# Microcontroller_CC1350.net
KiCad netlist of a schematic drawn in Altium Designer
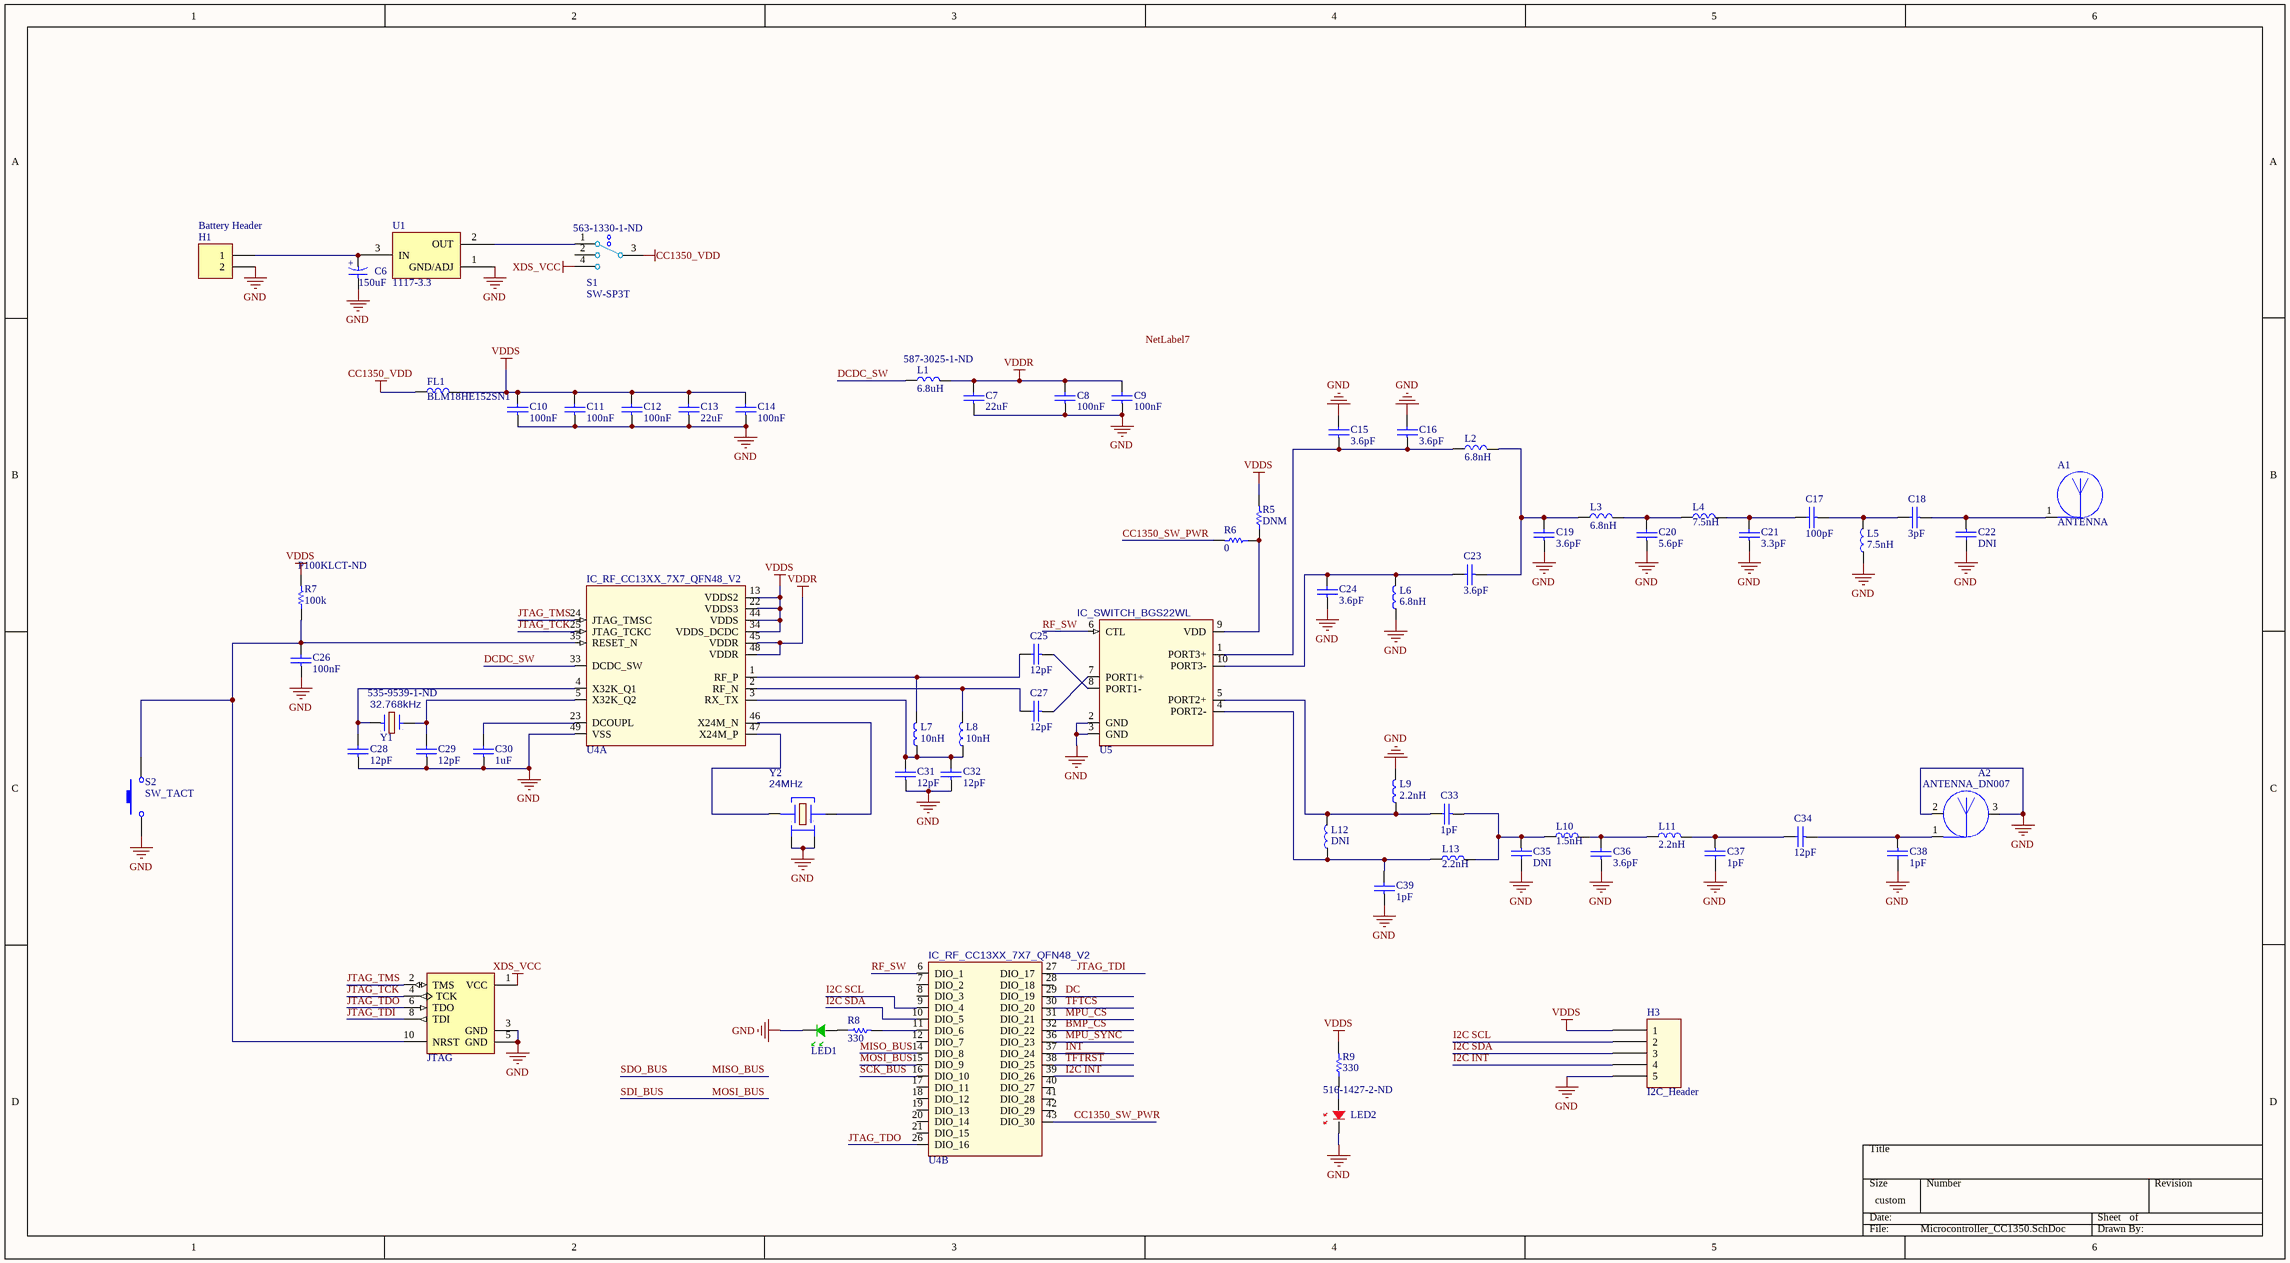
[diagram p0: Microcontroller_CC1350.SchDoc]

(export (version "E")
  (design (tool "Eeschema 10.0.6"))
  (components
    (comp (ref "A1")
      (value "ANTENNA")
      (footprint "Sub-1GHz-Antenna")
      (fields (field (name "DESIGNED BY") "Pawel Kwaskiewicz"))
      (libsource (lib "Biosense_Altium_Library") (part "ANTENNA"))
    )
    (comp (ref "A2")
      (value "ANTENNA_DN007")
      (footprint "Inverted_F_Antenna")
      (fields (field (name "DESIGNED BY") "Artur Bielinski"))
      (libsource (lib "Biosense_Altium_Library") (part "ANTENNA_DN007"))
    )
    (comp (ref "C6")
      (value "150uF")
      (footprint "2312 [IMP] Polar")
      (description "Capacitor")
      (libsource (lib "Biosense_Altium_Library") (part "Cap_E"))
    )
    (comp (ref "C7")
      (value "22uF")
      (footprint "0603[IMP]")
      (fields (field (name "VOLTAGE") "CMAX"))
      (libsource (lib "Biosense_Altium_Library") (part "CAPACITOR"))
    )
    (comp (ref "C8")
      (value "100nF")
      (footprint "0402[IMP]")
      (fields (field (name "VOLTAGE") "CMAX"))
      (libsource (lib "Biosense_Altium_Library") (part "CAPACITOR"))
    )
    (comp (ref "C9")
      (value "100nF")
      (footprint "0402[IMP]")
      (fields (field (name "VOLTAGE") "CMAX"))
      (libsource (lib "Biosense_Altium_Library") (part "CAPACITOR"))
    )
    (comp (ref "C10")
      (value "100nF")
      (footprint "0402[IMP]")
      (fields (field (name "VOLTAGE") "CMAX"))
      (libsource (lib "Biosense_Altium_Library") (part "CAPACITOR"))
    )
    (comp (ref "C11")
      (value "100nF")
      (footprint "0402[IMP]")
      (fields (field (name "VOLTAGE") "CMAX"))
      (libsource (lib "Biosense_Altium_Library") (part "CAPACITOR"))
    )
    (comp (ref "C12")
      (value "100nF")
      (footprint "0402[IMP]")
      (fields (field (name "VOLTAGE") "CMAX"))
      (libsource (lib "Biosense_Altium_Library") (part "CAPACITOR"))
    )
    (comp (ref "C13")
      (value "22uF")
      (footprint "0603[IMP]")
      (fields (field (name "VOLTAGE") "CMAX"))
      (libsource (lib "Biosense_Altium_Library") (part "CAPACITOR"))
    )
    (comp (ref "C14")
      (value "100nF")
      (footprint "0402[IMP]")
      (fields (field (name "VOLTAGE") "CMAX"))
      (libsource (lib "Biosense_Altium_Library") (part "CAPACITOR"))
    )
    (comp (ref "C15")
      (value "3.6pF")
      (footprint "0402[IMP]")
      (fields (field (name "VOLTAGE") "CMAX"))
      (libsource (lib "Biosense_Altium_Library") (part "CAPACITOR"))
    )
    (comp (ref "C16")
      (value "3.6pF")
      (footprint "0402[IMP]")
      (fields (field (name "VOLTAGE") "CMAX"))
      (libsource (lib "Biosense_Altium_Library") (part "CAPACITOR"))
    )
    (comp (ref "C17")
      (value "100pF")
      (footprint "0402[IMP]")
      (fields (field (name "VOLTAGE") "CMAX"))
      (libsource (lib "Biosense_Altium_Library") (part "CAPACITOR"))
    )
    (comp (ref "C18")
      (value "3pF")
      (footprint "0402[IMP]")
      (fields (field (name "VOLTAGE") "CMAX"))
      (libsource (lib "Biosense_Altium_Library") (part "CAPACITOR"))
    )
    (comp (ref "C19")
      (value "3.6pF")
      (footprint "0402[IMP]")
      (fields (field (name "VOLTAGE") "CMAX"))
      (libsource (lib "Biosense_Altium_Library") (part "CAPACITOR"))
    )
    (comp (ref "C20")
      (value "5.6pF")
      (footprint "0402[IMP]")
      (fields (field (name "VOLTAGE") "CMAX"))
      (libsource (lib "Biosense_Altium_Library") (part "CAPACITOR"))
    )
    (comp (ref "C21")
      (value "3.3pF")
      (footprint "0402[IMP]")
      (fields (field (name "VOLTAGE") "CMAX"))
      (libsource (lib "Biosense_Altium_Library") (part "CAPACITOR"))
    )
    (comp (ref "C22")
      (value "DNI")
      (footprint "0402[IMP]")
      (fields (field (name "VOLTAGE") "CMAX"))
      (libsource (lib "Biosense_Altium_Library") (part "CAPACITOR"))
    )
    (comp (ref "C23")
      (value "3.6pF")
      (footprint "0402[IMP]")
      (fields (field (name "VOLTAGE") "CMAX"))
      (libsource (lib "Biosense_Altium_Library") (part "CAPACITOR"))
    )
    (comp (ref "C24")
      (value "3.6pF")
      (footprint "0402[IMP]")
      (fields (field (name "VOLTAGE") "CMAX"))
      (libsource (lib "Biosense_Altium_Library") (part "CAPACITOR"))
    )
    (comp (ref "C25")
      (value "12pF")
      (footprint "0402[IMP]")
      (fields (field (name "VOLTAGE") "CMAX"))
      (libsource (lib "Biosense_Altium_Library") (part "CAPACITOR"))
    )
    (comp (ref "C26")
      (value "100nF")
      (footprint "0402[IMP]")
      (fields (field (name "VOLTAGE") "CMAX"))
      (libsource (lib "Biosense_Altium_Library") (part "CAPACITOR"))
    )
    (comp (ref "C27")
      (value "12pF")
      (footprint "0402[IMP]")
      (fields (field (name "VOLTAGE") "CMAX"))
      (libsource (lib "Biosense_Altium_Library") (part "CAPACITOR"))
    )
    (comp (ref "C28")
      (value "12pF")
      (footprint "0402[IMP]")
      (fields (field (name "VOLTAGE") "CMAX"))
      (libsource (lib "Biosense_Altium_Library") (part "CAPACITOR"))
    )
    (comp (ref "C29")
      (value "12pF")
      (footprint "0402[IMP]")
      (fields (field (name "VOLTAGE") "CMAX"))
      (libsource (lib "Biosense_Altium_Library") (part "CAPACITOR"))
    )
    (comp (ref "C30")
      (value "1uF")
      (footprint "0402[IMP]")
      (fields (field (name "VOLTAGE") "CMAX"))
      (libsource (lib "Biosense_Altium_Library") (part "CAPACITOR"))
    )
    (comp (ref "C31")
      (value "12pF")
      (footprint "0402[IMP]")
      (fields (field (name "VOLTAGE") "CMAX"))
      (libsource (lib "Biosense_Altium_Library") (part "CAPACITOR"))
    )
    (comp (ref "C32")
      (value "12pF")
      (footprint "0402[IMP]")
      (fields (field (name "VOLTAGE") "CMAX"))
      (libsource (lib "Biosense_Altium_Library") (part "CAPACITOR"))
    )
    (comp (ref "C33")
      (value "1pF")
      (footprint "0402[IMP]")
      (fields (field (name "VOLTAGE") "CMAX"))
      (libsource (lib "Biosense_Altium_Library") (part "CAPACITOR"))
    )
    (comp (ref "C34")
      (value "12pF")
      (footprint "0402[IMP]")
      (fields (field (name "VOLTAGE") "CMAX"))
      (libsource (lib "Biosense_Altium_Library") (part "CAPACITOR"))
    )
    (comp (ref "C35")
      (value "DNI")
      (footprint "0402[IMP]")
      (fields (field (name "VOLTAGE") "CMAX"))
      (libsource (lib "Biosense_Altium_Library") (part "CAPACITOR"))
    )
    (comp (ref "C36")
      (value "3.6pF")
      (footprint "0402[IMP]")
      (fields (field (name "VOLTAGE") "CMAX"))
      (libsource (lib "Biosense_Altium_Library") (part "CAPACITOR"))
    )
    (comp (ref "C37")
      (value "1pF")
      (footprint "0402[IMP]")
      (fields (field (name "VOLTAGE") "CMAX"))
      (libsource (lib "Biosense_Altium_Library") (part "CAPACITOR"))
    )
    (comp (ref "C38")
      (value "1pF")
      (footprint "0402[IMP]")
      (fields (field (name "VOLTAGE") "CMAX"))
      (libsource (lib "Biosense_Altium_Library") (part "CAPACITOR"))
    )
    (comp (ref "C39")
      (value "1pF")
      (footprint "0402[IMP]")
      (fields (field (name "VOLTAGE") "CMAX"))
      (libsource (lib "Biosense_Altium_Library") (part "CAPACITOR"))
    )
    (comp (ref "FL1")
      (value "BLM18HE152SN1")
      (footprint "0603[IMP]")
      (libsource (lib "Biosense_Altium_Library") (part "INDUCTOR"))
    )
    (comp (ref "H1")
      (value "Battery Header")
      (footprint "S2B-PH-SM4-TB")
      (libsource (lib "Biosense_Altium_Library") (part "Header 2"))
    )
    (comp (ref "H2")
      (value "JTAG")
      (footprint "HDR-2*5-0.05_Without_Through_Hole")
      (description "USB JTAG Programmer")
      (libsource (lib "Biosense_Altium_Library") (part "JTAG-ARM"))
    )
    (comp (ref "H3")
      (value "I2C_Header")
      (footprint "I2C_Header")
      (libsource (lib "Biosense_Altium_Library") (part "I2C_Header"))
    )
    (comp (ref "L1")
      (value "6.8uH")
      (footprint "0805[IMP]")
      (fields (field (name "SUPPLIER PART NUMBER 1") "587-3025-1-ND"))
      (libsource (lib "Biosense_Altium_Library") (part "INDUCTOR"))
    )
    (comp (ref "L2")
      (value "6.8nH")
      (footprint "0402[IMP]")
      (libsource (lib "Biosense_Altium_Library") (part "INDUCTOR"))
    )
    (comp (ref "L3")
      (value "6.8nH")
      (footprint "0402[IMP]")
      (libsource (lib "Biosense_Altium_Library") (part "INDUCTOR"))
    )
    (comp (ref "L4")
      (value "7.5nH")
      (footprint "0402[IMP]")
      (libsource (lib "Biosense_Altium_Library") (part "INDUCTOR"))
    )
    (comp (ref "L5")
      (value "7.5nH")
      (footprint "0402[IMP]")
      (libsource (lib "Biosense_Altium_Library") (part "INDUCTOR"))
    )
    (comp (ref "L6")
      (value "6.8nH")
      (footprint "0402[IMP]")
      (libsource (lib "Biosense_Altium_Library") (part "INDUCTOR"))
    )
    (comp (ref "L7")
      (value "10nH")
      (footprint "0402[IMP]")
      (libsource (lib "Biosense_Altium_Library") (part "INDUCTOR"))
    )
    (comp (ref "L8")
      (value "10nH")
      (footprint "0402[IMP]")
      (libsource (lib "Biosense_Altium_Library") (part "INDUCTOR"))
    )
    (comp (ref "L9")
      (value "2.2nH")
      (footprint "0402[IMP]")
      (libsource (lib "Biosense_Altium_Library") (part "INDUCTOR"))
    )
    (comp (ref "L10")
      (value "1.5nH")
      (footprint "0402[IMP]")
      (libsource (lib "Biosense_Altium_Library") (part "INDUCTOR"))
    )
    (comp (ref "L11")
      (value "2.2nH")
      (footprint "0402[IMP]")
      (libsource (lib "Biosense_Altium_Library") (part "INDUCTOR"))
    )
    (comp (ref "L12")
      (value "DNI")
      (footprint "0402[IMP]")
      (libsource (lib "Biosense_Altium_Library") (part "INDUCTOR"))
    )
    (comp (ref "L13")
      (value "2.2nH")
      (footprint "0402[IMP]")
      (libsource (lib "Biosense_Altium_Library") (part "INDUCTOR"))
    )
    (comp (ref "LED1")
      (value "LEDG")
      (footprint "0805[IMP] - POLAR")
      (description "LED")
      (libsource (lib "Biosense_Altium_Library") (part "LED_G"))
    )
    (comp (ref "LED2")
      (value "LEDR")
      (footprint "0805[IMP] - POLAR")
      (description "LED")
      (fields (field (name "SUPPLIER PART NUMBER 1") "516-1427-2-ND"))
      (libsource (lib "Biosense_Altium_Library") (part "LED_R"))
    )
    (comp (ref "R5")
      (value "DNM")
      (footprint "0402[IMP]")
      (libsource (lib "Biosense_Altium_Library") (part "RESISTOR"))
    )
    (comp (ref "R6")
      (value "0")
      (footprint "0402[IMP]")
      (libsource (lib "Biosense_Altium_Library") (part "RESISTOR"))
    )
    (comp (ref "R7")
      (value "100k")
      (footprint "0402[IMP]")
      (fields (field (name "SUPPLIER PART NUMBER 1") "P100KLCT-ND"))
      (libsource (lib "Biosense_Altium_Library") (part "RESISTOR"))
    )
    (comp (ref "R8")
      (value "330")
      (footprint "0402[IMP]")
      (libsource (lib "Biosense_Altium_Library") (part "RESISTOR"))
    )
    (comp (ref "R9")
      (value "330")
      (footprint "0402[IMP]")
      (libsource (lib "Biosense_Altium_Library") (part "RESISTOR"))
    )
    (comp (ref "S1")
      (value "SW-SP3T")
      (footprint "CL-SB-13B")
      (fields (field (name "SUPPLIER PART NUMBER 1") "563-1330-1-ND"))
      (libsource (lib "Biosense_Altium_Library") (part "SW-SP3T"))
    )
    (comp (ref "S2")
      (value "SW_TACT")
      (footprint "PTS645SH50SMTR92_LFS")
      (description "Tactile switch")
      (libsource (lib "Biosense_Altium_Library") (part "SW_TACT"))
    )
    (comp (ref "U1")
      (value "1117-3.3")
      (footprint "SOT-223")
      (description "3.3V Voltage Regulator")
      (libsource (lib "Biosense_Altium_Library") (part "1117-3.3V"))
    )
    (comp (ref "U4")
      (value "IC_RF_CC13XX_7X7_QFN48_V2")
      (footprint "RGZ(S-PVQFN-N48) - duplicate")
      (fields (field (name "DESIGNED_BY") "Artur Bielinski"))
      (libsource (lib "Biosense_Altium_Library") (part "IC_RF_CC13XX_7X7_QFN48_V2"))
    )
    (comp (ref "U5")
      (value "IC_SWITCH_BGS22WL")
      (footprint "TSLP-10-1")
      (fields (field (name "DESIGNED_BY") "Artur Bielinski"))
      (libsource (lib "Biosense_Altium_Library") (part "IC_SWITCH_XMSSJE3G0PA-00"))
    )
    (comp (ref "Y1")
      (value "32.768kHz")
      (footprint "FC-135")
      (fields (field (name "SUPPLIER PART NUMBER 1") "535-9539-1-ND"))
      (libsource (lib "Biosense_Altium_Library") (part "CRYSTAL"))
    )
    (comp (ref "Y2")
      (value "24MHz")
      (footprint "TSX-3225")
      (libsource (lib "Biosense_Altium_Library") (part "XTAL_4PIN_S"))
    )
  )
  (nets
    (net (code "1") (name "/BMP_CS") (class "Default")
      (node (ref "U4") (pin "32") (pinfunction "DIO_22_32") (pintype "bidirectional"))
    )
    (net (code "2") (name "/CC1350_SW_PWR") (class "Default")
      (node (ref "R6") (pin "2") (pinfunction "2_2") (pintype "passive"))
      (node (ref "U4") (pin "43") (pinfunction "DIO_30_43") (pintype "bidirectional"))
    )
    (net (code "3") (name "/DC") (class "Default")
      (node (ref "U4") (pin "29") (pinfunction "DIO_19_29") (pintype "bidirectional"))
    )
    (net (code "4") (name "/DCDC_SW") (class "Default")
      (node (ref "L1") (pin "1") (pinfunction "1_1") (pintype "passive"))
      (node (ref "U4") (pin "33") (pinfunction "DCDC_SW_33") (pintype "power_in"))
    )
    (net (code "5") (name "/I2C INT") (class "Default")
      (node (ref "H3") (pin "4") (pinfunction "4_4") (pintype "passive"))
      (node (ref "U4") (pin "39") (pinfunction "DIO_26_39") (pintype "bidirectional"))
    )
    (net (code "6") (name "/I2C SCL") (class "Default")
      (node (ref "H3") (pin "2") (pinfunction "2_2") (pintype "passive"))
      (node (ref "U4") (pin "9") (pinfunction "DIO_4_9") (pintype "bidirectional"))
    )
    (net (code "7") (name "/I2C SDA") (class "Default")
      (node (ref "H3") (pin "3") (pinfunction "3_3") (pintype "passive"))
      (node (ref "U4") (pin "10") (pinfunction "DIO_5_10") (pintype "bidirectional"))
    )
    (net (code "8") (name "/INT") (class "Default")
      (node (ref "U4") (pin "37") (pinfunction "DIO_24_37") (pintype "bidirectional"))
    )
    (net (code "9") (name "/JTAG_TCK") (class "Default")
      (node (ref "H2") (pin "4") (pinfunction "TCK_4") (pintype "output"))
      (node (ref "U4") (pin "25") (pinfunction "JTAG_TCKC_25") (pintype "input"))
    )
    (net (code "10") (name "/JTAG_TDI") (class "Default")
      (node (ref "H2") (pin "8") (pinfunction "TDI_8") (pintype "output"))
      (node (ref "U4") (pin "27") (pinfunction "DIO_17_27") (pintype "bidirectional"))
    )
    (net (code "11") (name "/JTAG_TDO") (class "Default")
      (node (ref "H2") (pin "6") (pinfunction "TDO_6") (pintype "input"))
      (node (ref "U4") (pin "26") (pinfunction "DIO_16_26") (pintype "bidirectional"))
    )
    (net (code "12") (name "/JTAG_TMS") (class "Default")
      (node (ref "H2") (pin "2") (pinfunction "TMS_2") (pintype "bidirectional"))
      (node (ref "U4") (pin "24") (pinfunction "JTAG_TMSC_24") (pintype "input"))
    )
    (net (code "13") (name "/MISO_BUS") (class "Default")
      (node (ref "U4") (pin "14") (pinfunction "DIO_8_14") (pintype "bidirectional"))
    )
    (net (code "14") (name "/MOSI_BUS") (class "Default")
      (node (ref "U4") (pin "15") (pinfunction "DIO_9_15") (pintype "bidirectional"))
    )
    (net (code "15") (name "/MPU_CS") (class "Default")
      (node (ref "U4") (pin "31") (pinfunction "DIO_21_31") (pintype "bidirectional"))
    )
    (net (code "16") (name "/MPU_SYNC") (class "Default")
      (node (ref "U4") (pin "36") (pinfunction "DIO_23_36") (pintype "bidirectional"))
    )
    (net (code "18") (name "/RF_SW") (class "Default")
      (node (ref "U4") (pin "6") (pinfunction "DIO_1_6") (pintype "bidirectional"))
      (node (ref "U5") (pin "6") (pinfunction "CTL_6") (pintype "input"))
    )
    (net (code "19") (name "/SCK_BUS") (class "Default")
      (node (ref "U4") (pin "16") (pinfunction "DIO_10_16") (pintype "bidirectional"))
    )
    (net (code "20") (name "/TFTCS") (class "Default")
      (node (ref "U4") (pin "30") (pinfunction "DIO_20_30") (pintype "bidirectional"))
    )
    (net (code "21") (name "/~{TFTRST}") (class "Default")
      (node (ref "U4") (pin "38") (pinfunction "DIO_25_38") (pintype "bidirectional"))
    )
    (net (code "22") (name "CC1350_VDD") (class "Default")
      (node (ref "FL1") (pin "1") (pinfunction "1_1") (pintype "passive"))
      (node (ref "S1") (pin "3") (pinfunction "3_3") (pintype "passive"))
    )
    (net (code "23") (name "GND") (class "Default")
      (node (ref "A2") (pin "2") (pinfunction "GND_2_2") (pintype "passive"))
      (node (ref "A2") (pin "3") (pinfunction "GND_3_3") (pintype "passive"))
      (node (ref "C10") (pin "2") (pinfunction "2_2") (pintype "passive"))
      (node (ref "C11") (pin "2") (pinfunction "2_2") (pintype "passive"))
      (node (ref "C12") (pin "2") (pinfunction "2_2") (pintype "passive"))
      (node (ref "C13") (pin "2") (pinfunction "2_2") (pintype "passive"))
      (node (ref "C14") (pin "2") (pinfunction "2_2") (pintype "passive"))
      (node (ref "C15") (pin "1") (pinfunction "1_1") (pintype "passive"))
      (node (ref "C16") (pin "1") (pinfunction "1_1") (pintype "passive"))
      (node (ref "C19") (pin "2") (pinfunction "2_2") (pintype "passive"))
      (node (ref "C20") (pin "2") (pinfunction "2_2") (pintype "passive"))
      (node (ref "C21") (pin "2") (pinfunction "2_2") (pintype "passive"))
      (node (ref "C22") (pin "1") (pinfunction "1_1") (pintype "passive"))
      (node (ref "C24") (pin "2") (pinfunction "2_2") (pintype "passive"))
      (node (ref "C26") (pin "2") (pinfunction "2_2") (pintype "passive"))
      (node (ref "C28") (pin "2") (pinfunction "2_2") (pintype "passive"))
      (node (ref "C29") (pin "2") (pinfunction "2_2") (pintype "passive"))
      (node (ref "C30") (pin "2") (pinfunction "2_2") (pintype "passive"))
      (node (ref "C31") (pin "2") (pinfunction "2_2") (pintype "passive"))
      (node (ref "C32") (pin "2") (pinfunction "2_2") (pintype "passive"))
      (node (ref "C35") (pin "1") (pinfunction "1_1") (pintype "passive"))
      (node (ref "C36") (pin "2") (pinfunction "2_2") (pintype "passive"))
      (node (ref "C37") (pin "1") (pinfunction "1_1") (pintype "passive"))
      (node (ref "C38") (pin "1") (pinfunction "1_1") (pintype "passive"))
      (node (ref "C39") (pin "2") (pinfunction "2_2") (pintype "passive"))
      (node (ref "C6") (pin "1") (pinfunction "1_1") (pintype "passive"))
      (node (ref "C7") (pin "2") (pinfunction "2_2") (pintype "passive"))
      (node (ref "C8") (pin "2") (pinfunction "2_2") (pintype "passive"))
      (node (ref "C9") (pin "2") (pinfunction "2_2") (pintype "passive"))
      (node (ref "H1") (pin "2") (pinfunction "2_2") (pintype "passive"))
      (node (ref "H2") (pin "3") (pinfunction "GND_3") (pintype "power_in"))
      (node (ref "H2") (pin "5") (pinfunction "GND_5") (pintype "power_in"))
      (node (ref "H3") (pin "5") (pinfunction "5_5") (pintype "passive"))
      (node (ref "L5") (pin "1") (pinfunction "1_1") (pintype "passive"))
      (node (ref "L6") (pin "1") (pinfunction "1_1") (pintype "passive"))
      (node (ref "L9") (pin "2") (pinfunction "2_2") (pintype "passive"))
      (node (ref "LED1") (pin "2") (pinfunction "K_2") (pintype "passive"))
      (node (ref "LED2") (pin "2") (pinfunction "K_2") (pintype "passive"))
      (node (ref "S2") (pin "1") (pinfunction "1_1") (pintype "passive"))
      (node (ref "U1") (pin "1") (pinfunction "GND/ADJ_1") (pintype "passive"))
      (node (ref "U4") (pin "49") (pinfunction "VSS_49") (pintype "power_in"))
      (node (ref "U5") (pin "2") (pinfunction "GND_2") (pintype "power_in"))
      (node (ref "U5") (pin "3") (pinfunction "GND_3") (pintype "power_in"))
      (node (ref "Y2") (pin "2") (pinfunction "2_2") (pintype "power_in"))
      (node (ref "Y2") (pin "4") (pinfunction "4_4") (pintype "power_in"))
    )
    (net (code "24") (name "Net-(A1-FEED{slash}GND_1)") (class "Default")
      (node (ref "A1") (pin "1") (pinfunction "FEED/GND_1_1") (pintype "passive"))
      (node (ref "C18") (pin "2") (pinfunction "2_2") (pintype "passive"))
      (node (ref "C22") (pin "2") (pinfunction "2_2") (pintype "passive"))
    )
    (net (code "25") (name "Net-(A2-FEED_1)") (class "Default")
      (node (ref "A2") (pin "1") (pinfunction "FEED_1_1") (pintype "passive"))
      (node (ref "C34") (pin "2") (pinfunction "2_2") (pintype "passive"))
      (node (ref "C38") (pin "2") (pinfunction "2_2") (pintype "passive"))
    )
    (net (code "26") (name "Net-(C17-Pad1)") (class "Default")
      (node (ref "C17") (pin "1") (pinfunction "1_1") (pintype "passive"))
      (node (ref "C21") (pin "1") (pinfunction "1_1") (pintype "passive"))
      (node (ref "L4") (pin "2") (pinfunction "2_2") (pintype "passive"))
    )
    (net (code "27") (name "Net-(C17-Pad2)") (class "Default")
      (node (ref "C17") (pin "2") (pinfunction "2_2") (pintype "passive"))
      (node (ref "C18") (pin "1") (pinfunction "1_1") (pintype "passive"))
      (node (ref "L5") (pin "2") (pinfunction "2_2") (pintype "passive"))
    )
    (net (code "28") (name "Net-(C19-Pad1)") (class "Default")
      (node (ref "C19") (pin "1") (pinfunction "1_1") (pintype "passive"))
      (node (ref "C23") (pin "2") (pinfunction "2_2") (pintype "passive"))
      (node (ref "L2") (pin "2") (pinfunction "2_2") (pintype "passive"))
      (node (ref "L3") (pin "1") (pinfunction "1_1") (pintype "passive"))
    )
    (net (code "29") (name "Net-(C20-Pad1)") (class "Default")
      (node (ref "C20") (pin "1") (pinfunction "1_1") (pintype "passive"))
      (node (ref "L3") (pin "2") (pinfunction "2_2") (pintype "passive"))
      (node (ref "L4") (pin "1") (pinfunction "1_1") (pintype "passive"))
    )
    (net (code "30") (name "Net-(C33-Pad2)") (class "Default")
      (node (ref "C33") (pin "2") (pinfunction "2_2") (pintype "passive"))
      (node (ref "C35") (pin "2") (pinfunction "2_2") (pintype "passive"))
      (node (ref "L10") (pin "1") (pinfunction "1_1") (pintype "passive"))
      (node (ref "L13") (pin "2") (pinfunction "2_2") (pintype "passive"))
    )
    (net (code "31") (name "Net-(C34-Pad1)") (class "Default")
      (node (ref "C34") (pin "1") (pinfunction "1_1") (pintype "passive"))
      (node (ref "C37") (pin "2") (pinfunction "2_2") (pintype "passive"))
      (node (ref "L11") (pin "2") (pinfunction "2_2") (pintype "passive"))
    )
    (net (code "32") (name "Net-(C36-Pad1)") (class "Default")
      (node (ref "C36") (pin "1") (pinfunction "1_1") (pintype "passive"))
      (node (ref "L10") (pin "2") (pinfunction "2_2") (pintype "passive"))
      (node (ref "L11") (pin "1") (pinfunction "1_1") (pintype "passive"))
    )
    (net (code "33") (name "Net-(H2-NRST)") (class "Default")
      (node (ref "C26") (pin "1") (pinfunction "1_1") (pintype "passive"))
      (node (ref "H2") (pin "10") (pinfunction "NRST_10") (pintype "passive"))
      (node (ref "R7") (pin "1") (pinfunction "1_1") (pintype "passive"))
      (node (ref "S2") (pin "2") (pinfunction "2_2") (pintype "passive"))
      (node (ref "U4") (pin "35") (pinfunction "RESET_N_35") (pintype "input"))
    )
    (net (code "34") (name "Net-(LED1-A)") (class "Default")
      (node (ref "LED1") (pin "1") (pinfunction "A_1") (pintype "passive"))
      (node (ref "R8") (pin "1") (pinfunction "1_1") (pintype "passive"))
    )
    (net (code "35") (name "Net-(LED2-A)") (class "Default")
      (node (ref "LED2") (pin "1") (pinfunction "A_1") (pintype "passive"))
      (node (ref "R9") (pin "1") (pinfunction "1_1") (pintype "passive"))
    )
    (net (code "36") (name "Net-(U1-IN)") (class "Default")
      (node (ref "C6") (pin "2") (pinfunction "2_2") (pintype "passive"))
      (node (ref "H1") (pin "1") (pinfunction "1_1") (pintype "passive"))
      (node (ref "U1") (pin "3") (pinfunction "IN_3") (pintype "passive"))
    )
    (net (code "37") (name "Net-(U1-OUT)") (class "Default")
      (node (ref "S1") (pin "1") (pinfunction "1_1") (pintype "passive"))
      (node (ref "U1") (pin "2") (pinfunction "OUT_2") (pintype "passive"))
    )
    (net (code "38") (name "Net-(U4A-DCOUPL)") (class "Default")
      (node (ref "C30") (pin "1") (pinfunction "1_1") (pintype "passive"))
      (node (ref "U4") (pin "23") (pinfunction "DCOUPL_23") (pintype "passive"))
    )
    (net (code "39") (name "Net-(U4A-RF_N)") (class "Default")
      (node (ref "C27") (pin "1") (pinfunction "1_1") (pintype "passive"))
      (node (ref "L8") (pin "2") (pinfunction "2_2") (pintype "passive"))
      (node (ref "U4") (pin "2") (pinfunction "RF_N_2") (pintype "passive"))
    )
    (net (code "40") (name "Net-(U4A-RF_P)") (class "Default")
      (node (ref "C25") (pin "1") (pinfunction "1_1") (pintype "passive"))
      (node (ref "L7") (pin "2") (pinfunction "2_2") (pintype "passive"))
      (node (ref "U4") (pin "1") (pinfunction "RF_P_1") (pintype "passive"))
    )
    (net (code "41") (name "Net-(U4A-RX_TX)") (class "Default")
      (node (ref "C31") (pin "1") (pinfunction "1_1") (pintype "passive"))
      (node (ref "C32") (pin "1") (pinfunction "1_1") (pintype "passive"))
      (node (ref "L7") (pin "1") (pinfunction "1_1") (pintype "passive"))
      (node (ref "L8") (pin "1") (pinfunction "1_1") (pintype "passive"))
      (node (ref "U4") (pin "3") (pinfunction "RX_TX_3") (pintype "bidirectional"))
    )
    (net (code "42") (name "Net-(U4A-X24M_N)") (class "Default")
      (node (ref "U4") (pin "46") (pinfunction "X24M_N_46") (pintype "passive"))
      (node (ref "Y2") (pin "3") (pinfunction "3_3") (pintype "passive"))
    )
    (net (code "43") (name "Net-(U4A-X24M_P)") (class "Default")
      (node (ref "U4") (pin "47") (pinfunction "X24M_P_47") (pintype "passive"))
      (node (ref "Y2") (pin "1") (pinfunction "1_1") (pintype "passive"))
    )
    (net (code "44") (name "Net-(U4A-X32K_Q1)") (class "Default")
      (node (ref "C28") (pin "1") (pinfunction "1_1") (pintype "passive"))
      (node (ref "U4") (pin "4") (pinfunction "X32K_Q1_4") (pintype "passive"))
      (node (ref "Y1") (pin "1") (pinfunction "1_1") (pintype "passive"))
    )
    (net (code "45") (name "Net-(U4A-X32K_Q2)") (class "Default")
      (node (ref "C29") (pin "1") (pinfunction "1_1") (pintype "passive"))
      (node (ref "U4") (pin "5") (pinfunction "X32K_Q2_5") (pintype "passive"))
      (node (ref "Y1") (pin "2") (pinfunction "2_2") (pintype "passive"))
    )
    (net (code "46") (name "Net-(U4B-DIO_6)") (class "Default")
      (node (ref "R8") (pin "2") (pinfunction "2_2") (pintype "passive"))
      (node (ref "U4") (pin "11") (pinfunction "DIO_6_11") (pintype "bidirectional"))
    )
    (net (code "47") (name "Net-(U5-PORT1+)") (class "Default")
      (node (ref "C27") (pin "2") (pinfunction "2_2") (pintype "passive"))
      (node (ref "U5") (pin "7") (pinfunction "PORT1+_7") (pintype "passive"))
    )
    (net (code "48") (name "Net-(U5-PORT1-)") (class "Default")
      (node (ref "C25") (pin "2") (pinfunction "2_2") (pintype "passive"))
      (node (ref "U5") (pin "8") (pinfunction "PORT1-_8") (pintype "passive"))
    )
    (net (code "49") (name "Net-(U5-PORT2+)") (class "Default")
      (node (ref "C33") (pin "1") (pinfunction "1_1") (pintype "passive"))
      (node (ref "L12") (pin "2") (pinfunction "2_2") (pintype "passive"))
      (node (ref "L9") (pin "1") (pinfunction "1_1") (pintype "passive"))
      (node (ref "U5") (pin "5") (pinfunction "PORT2+_5") (pintype "passive"))
    )
    (net (code "50") (name "Net-(U5-PORT2-)") (class "Default")
      (node (ref "C39") (pin "1") (pinfunction "1_1") (pintype "passive"))
      (node (ref "L12") (pin "1") (pinfunction "1_1") (pintype "passive"))
      (node (ref "L13") (pin "1") (pinfunction "1_1") (pintype "passive"))
      (node (ref "U5") (pin "4") (pinfunction "PORT2-_4") (pintype "passive"))
    )
    (net (code "51") (name "Net-(U5-PORT3+)") (class "Default")
      (node (ref "C15") (pin "2") (pinfunction "2_2") (pintype "passive"))
      (node (ref "C16") (pin "2") (pinfunction "2_2") (pintype "passive"))
      (node (ref "L2") (pin "1") (pinfunction "1_1") (pintype "passive"))
      (node (ref "U5") (pin "1") (pinfunction "PORT3+_1") (pintype "passive"))
    )
    (net (code "52") (name "Net-(U5-PORT3-)") (class "Default")
      (node (ref "C23") (pin "1") (pinfunction "1_1") (pintype "passive"))
      (node (ref "C24") (pin "1") (pinfunction "1_1") (pintype "passive"))
      (node (ref "L6") (pin "2") (pinfunction "2_2") (pintype "passive"))
      (node (ref "U5") (pin "10") (pinfunction "PORT3-_10") (pintype "passive"))
    )
    (net (code "53") (name "Net-(U5-VDD)") (class "Default")
      (node (ref "R5") (pin "1") (pinfunction "1_1") (pintype "passive"))
      (node (ref "R6") (pin "1") (pinfunction "1_1") (pintype "passive"))
      (node (ref "U5") (pin "9") (pinfunction "VDD_9") (pintype "power_in"))
    )
    (net (code "54") (name "VDDR") (class "Default")
      (node (ref "C7") (pin "1") (pinfunction "1_1") (pintype "passive"))
      (node (ref "C8") (pin "1") (pinfunction "1_1") (pintype "passive"))
      (node (ref "C9") (pin "1") (pinfunction "1_1") (pintype "passive"))
      (node (ref "L1") (pin "2") (pinfunction "2_2") (pintype "passive"))
      (node (ref "U4") (pin "45") (pinfunction "VDDR_45") (pintype "power_in"))
      (node (ref "U4") (pin "48") (pinfunction "VDDR_48") (pintype "power_in"))
    )
    (net (code "55") (name "VDDS") (class "Default")
      (node (ref "C10") (pin "1") (pinfunction "1_1") (pintype "passive"))
      (node (ref "C11") (pin "1") (pinfunction "1_1") (pintype "passive"))
      (node (ref "C12") (pin "1") (pinfunction "1_1") (pintype "passive"))
      (node (ref "C13") (pin "1") (pinfunction "1_1") (pintype "passive"))
      (node (ref "C14") (pin "1") (pinfunction "1_1") (pintype "passive"))
      (node (ref "FL1") (pin "2") (pinfunction "2_2") (pintype "passive"))
      (node (ref "H3") (pin "1") (pinfunction "1_1") (pintype "passive"))
      (node (ref "R5") (pin "2") (pinfunction "2_2") (pintype "passive"))
      (node (ref "R7") (pin "2") (pinfunction "2_2") (pintype "passive"))
      (node (ref "R9") (pin "2") (pinfunction "2_2") (pintype "passive"))
      (node (ref "U4") (pin "13") (pinfunction "VDDS2_13") (pintype "power_in"))
      (node (ref "U4") (pin "22") (pinfunction "VDDS3_22") (pintype "power_in"))
      (node (ref "U4") (pin "34") (pinfunction "VDDS_DCDC_34") (pintype "power_in"))
      (node (ref "U4") (pin "44") (pinfunction "VDDS_44") (pintype "power_in"))
    )
    (net (code "56") (name "XDS_VCC") (class "Default")
      (node (ref "H2") (pin "1") (pinfunction "VCC_1") (pintype "power_in"))
      (node (ref "S1") (pin "4") (pinfunction "4_4") (pintype "passive"))
    )
    (net (code "57") (name "unconnected-(S1-Pad2)") (class "Default")
      (node (ref "S1") (pin "2") (pinfunction "2_2") (pintype "passive"))
    )
    (net (code "58") (name "unconnected-(U4B-DIO_2-Pad7)") (class "Default")
      (node (ref "U4") (pin "7") (pinfunction "DIO_2_7") (pintype "bidirectional"))
    )
    (net (code "59") (name "unconnected-(U4B-DIO_3-Pad8)") (class "Default")
      (node (ref "U4") (pin "8") (pinfunction "DIO_3_8") (pintype "bidirectional"))
    )
    (net (code "60") (name "unconnected-(U4B-DIO_7-Pad12)") (class "Default")
      (node (ref "U4") (pin "12") (pinfunction "DIO_7_12") (pintype "bidirectional"))
    )
    (net (code "61") (name "unconnected-(U4B-DIO_11-Pad17)") (class "Default")
      (node (ref "U4") (pin "17") (pinfunction "DIO_11_17") (pintype "bidirectional"))
    )
    (net (code "62") (name "unconnected-(U4B-DIO_12-Pad18)") (class "Default")
      (node (ref "U4") (pin "18") (pinfunction "DIO_12_18") (pintype "bidirectional"))
    )
    (net (code "63") (name "unconnected-(U4B-DIO_13-Pad19)") (class "Default")
      (node (ref "U4") (pin "19") (pinfunction "DIO_13_19") (pintype "bidirectional"))
    )
    (net (code "64") (name "unconnected-(U4B-DIO_14-Pad20)") (class "Default")
      (node (ref "U4") (pin "20") (pinfunction "DIO_14_20") (pintype "bidirectional"))
    )
    (net (code "65") (name "unconnected-(U4B-DIO_15-Pad21)") (class "Default")
      (node (ref "U4") (pin "21") (pinfunction "DIO_15_21") (pintype "bidirectional"))
    )
    (net (code "66") (name "unconnected-(U4B-DIO_18-Pad28)") (class "Default")
      (node (ref "U4") (pin "28") (pinfunction "DIO_18_28") (pintype "bidirectional"))
    )
    (net (code "67") (name "unconnected-(U4B-DIO_27-Pad40)") (class "Default")
      (node (ref "U4") (pin "40") (pinfunction "DIO_27_40") (pintype "bidirectional"))
    )
    (net (code "68") (name "unconnected-(U4B-DIO_28-Pad41)") (class "Default")
      (node (ref "U4") (pin "41") (pinfunction "DIO_28_41") (pintype "bidirectional"))
    )
    (net (code "69") (name "unconnected-(U4B-DIO_29-Pad42)") (class "Default")
      (node (ref "U4") (pin "42") (pinfunction "DIO_29_42") (pintype "bidirectional"))
    )
  )
)
